# imu_base.net
KiCad netlist of a schematic drawn in EAGLE
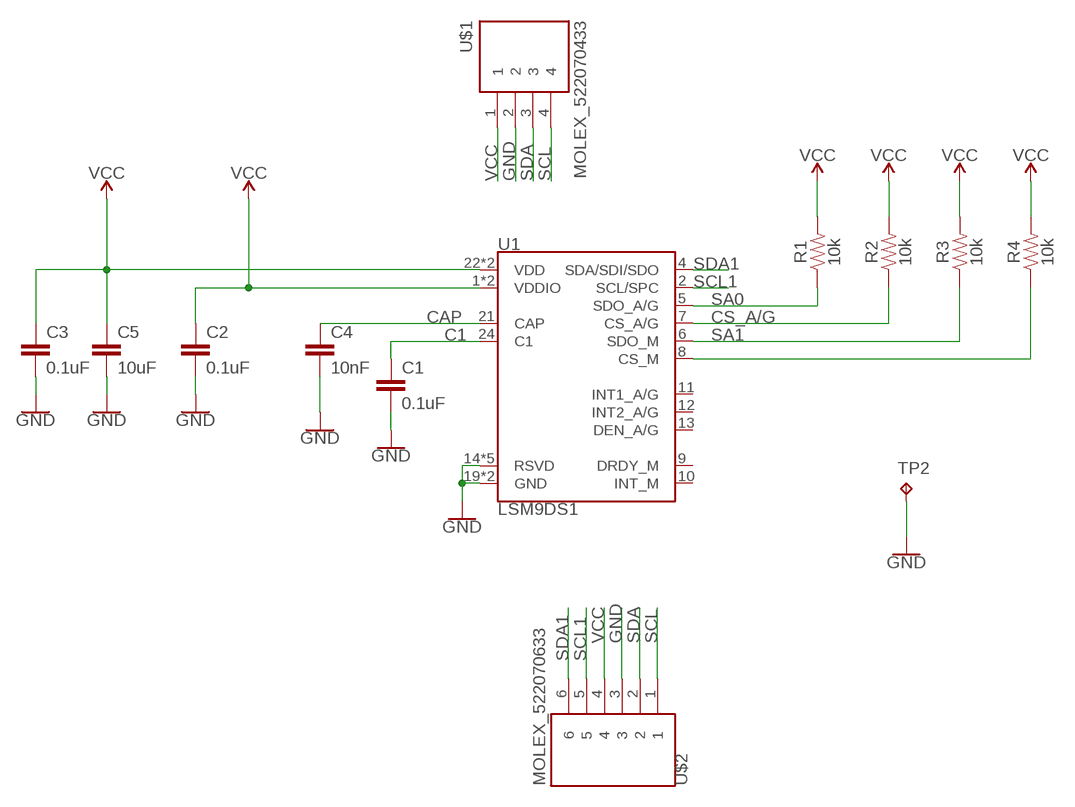
[diagram p0: schematic, sheet 1]

(export (version "E")
  (design (tool "Eeschema 10.0.6"))
  (components
    (comp (ref "C1")
      (value "0.1uF")
      (footprint "eagle-import:0603")
      (libsource (lib "eagle-import") (part "0.1UF-0603-25V-(+80/-20%)"))
    )
    (comp (ref "C2")
      (value "0.1uF")
      (footprint "eagle-import:0603")
      (libsource (lib "eagle-import") (part "0.1UF-0603-25V-(+80/-20%)"))
    )
    (comp (ref "C3")
      (value "0.1uF")
      (footprint "eagle-import:0603")
      (libsource (lib "eagle-import") (part "0.1UF-0603-25V-(+80/-20%)"))
    )
    (comp (ref "C4")
      (value "10nF")
      (footprint "eagle-import:0603")
      (libsource (lib "eagle-import") (part "10NF-0603-50V-10%"))
    )
    (comp (ref "C5")
      (value "10uF")
      (footprint "eagle-import:0603")
      (libsource (lib "eagle-import") (part "10UF-0603-6.3V-20%"))
    )
    (comp (ref "R1")
      (value "10k")
      (footprint "eagle-import:0603")
      (libsource (lib "eagle-import") (part "10KOHM-0603-1/10W-1%"))
    )
    (comp (ref "R2")
      (value "10k")
      (footprint "eagle-import:0603")
      (libsource (lib "eagle-import") (part "10KOHM-0603-1/10W-1%"))
    )
    (comp (ref "R3")
      (value "10k")
      (footprint "eagle-import:0603")
      (libsource (lib "eagle-import") (part "10KOHM-0603-1/10W-1%"))
    )
    (comp (ref "R4")
      (value "10k")
      (footprint "eagle-import:0603")
      (libsource (lib "eagle-import") (part "10KOHM-0603-1/10W-1%"))
    )
    (comp (ref "TP2")
      (value "TPB2,54")
      (footprint "eagle-import:B2,54")
      (libsource (lib "eagle-import") (part "TPB2,54"))
    )
    (comp (ref "U$1")
      (value "MOLEX_522070433")
      (footprint "eagle-import:MOLEX4_1MM")
      (libsource (lib "eagle-import") (part "MOLEX_522070433"))
    )
    (comp (ref "U$2")
      (value "MOLEX_522070633")
      (footprint "eagle-import:MOLEX6_1MM")
      (libsource (lib "eagle-import") (part "MOLEX_522070633"))
    )
    (comp (ref "U1")
      (value "LSM9DS1")
      (footprint "eagle-import:LGA-24-3.5X3")
      (libsource (lib "eagle-import") (part "LSM9DS1"))
    )
  )
  (nets
    (net (code "1") (name "/C1") (class "Default")
      (node (ref "C1") (pin "1") (pinfunction "1_1") (pintype "passive"))
      (node (ref "U1") (pin "24") (pinfunction "C1_24") (pintype "bidirectional"))
    )
    (net (code "2") (name "/CAP") (class "Default")
      (node (ref "C4") (pin "1") (pinfunction "1_1") (pintype "passive"))
      (node (ref "U1") (pin "21") (pinfunction "CAP_21") (pintype "bidirectional"))
    )
    (net (code "3") (name "/CS_A{slash}G") (class "Default")
      (node (ref "R2") (pin "1") (pinfunction "1_1") (pintype "passive"))
      (node (ref "U1") (pin "7") (pinfunction "CS_A/G_7") (pintype "bidirectional"))
    )
    (net (code "4") (name "/SA0") (class "Default")
      (node (ref "R1") (pin "1") (pinfunction "1_1") (pintype "passive"))
      (node (ref "U1") (pin "5") (pinfunction "SDO_A/G_5") (pintype "bidirectional"))
    )
    (net (code "5") (name "/SA1") (class "Default")
      (node (ref "R3") (pin "1") (pinfunction "1_1") (pintype "passive"))
      (node (ref "U1") (pin "6") (pinfunction "SDO_M_6") (pintype "bidirectional"))
    )
    (net (code "6") (name "/SCL") (class "Default")
      (node (ref "U$1") (pin "4") (pinfunction "4_4") (pintype "passive"))
      (node (ref "U$2") (pin "1") (pinfunction "1_1") (pintype "bidirectional"))
    )
    (net (code "7") (name "/SCL1") (class "Default")
      (node (ref "U$2") (pin "5") (pinfunction "5_5") (pintype "bidirectional"))
      (node (ref "U1") (pin "2") (pinfunction "SCL/SPC_2") (pintype "bidirectional"))
    )
    (net (code "8") (name "/SDA") (class "Default")
      (node (ref "U$1") (pin "3") (pinfunction "3_3") (pintype "passive"))
      (node (ref "U$2") (pin "2") (pinfunction "2_2") (pintype "bidirectional"))
    )
    (net (code "9") (name "/SDA1") (class "Default")
      (node (ref "U$2") (pin "6") (pinfunction "6_6") (pintype "bidirectional"))
      (node (ref "U1") (pin "4") (pinfunction "SDA/SDI/SDO_4") (pintype "bidirectional"))
    )
    (net (code "10") (name "GND") (class "Default")
      (node (ref "C1") (pin "2") (pinfunction "2_2") (pintype "passive"))
      (node (ref "C2") (pin "2") (pinfunction "2_2") (pintype "passive"))
      (node (ref "C3") (pin "2") (pinfunction "2_2") (pintype "passive"))
      (node (ref "C4") (pin "2") (pinfunction "2_2") (pintype "passive"))
      (node (ref "C5") (pin "2") (pinfunction "2_2") (pintype "passive"))
      (node (ref "TP2") (pin "TP") (pinfunction "TP_TP") (pintype "input"))
      (node (ref "U$1") (pin "2") (pinfunction "2_2") (pintype "passive"))
      (node (ref "U$2") (pin "3") (pinfunction "3_3") (pintype "bidirectional"))
      (node (ref "U1") (pin "14") (pinfunction "RSVD_14") (pintype "bidirectional"))
      (node (ref "U1") (pin "15") (pinfunction "RSVD_15") (pintype "bidirectional"))
      (node (ref "U1") (pin "16") (pinfunction "RSVD_16") (pintype "bidirectional"))
      (node (ref "U1") (pin "17") (pinfunction "RSVD_17") (pintype "bidirectional"))
      (node (ref "U1") (pin "18") (pinfunction "RSVD_18") (pintype "bidirectional"))
      (node (ref "U1") (pin "19") (pinfunction "GND_19") (pintype "bidirectional"))
      (node (ref "U1") (pin "20") (pinfunction "GND_20") (pintype "bidirectional"))
    )
    (net (code "11") (name "Net-(U1-CS_M)") (class "Default")
      (node (ref "R4") (pin "1") (pinfunction "1_1") (pintype "passive"))
      (node (ref "U1") (pin "8") (pinfunction "CS_M_8") (pintype "bidirectional"))
    )
    (net (code "12") (name "VCC") (class "Default")
      (node (ref "C2") (pin "1") (pinfunction "1_1") (pintype "passive"))
      (node (ref "C3") (pin "1") (pinfunction "1_1") (pintype "passive"))
      (node (ref "C5") (pin "1") (pinfunction "1_1") (pintype "passive"))
      (node (ref "R1") (pin "2") (pinfunction "2_2") (pintype "passive"))
      (node (ref "R2") (pin "2") (pinfunction "2_2") (pintype "passive"))
      (node (ref "R3") (pin "2") (pinfunction "2_2") (pintype "passive"))
      (node (ref "R4") (pin "2") (pinfunction "2_2") (pintype "passive"))
      (node (ref "U$1") (pin "1") (pinfunction "1_1") (pintype "passive"))
      (node (ref "U$2") (pin "4") (pinfunction "4_4") (pintype "bidirectional"))
      (node (ref "U1") (pin "1") (pinfunction "VDDIO_1") (pintype "bidirectional"))
      (node (ref "U1") (pin "22") (pinfunction "VDD_22") (pintype "bidirectional"))
      (node (ref "U1") (pin "23") (pinfunction "VDD_23") (pintype "bidirectional"))
      (node (ref "U1") (pin "3") (pinfunction "VDDIO_3") (pintype "bidirectional"))
    )
    (net (code "13") (name "unconnected-(U1-DEN_A{slash}G-Pad13)") (class "Default")
      (node (ref "U1") (pin "13") (pinfunction "DEN_A/G_13") (pintype "bidirectional"))
    )
    (net (code "14") (name "unconnected-(U1-DRDY_M-Pad9)") (class "Default")
      (node (ref "U1") (pin "9") (pinfunction "DRDY_M_9") (pintype "bidirectional"))
    )
    (net (code "15") (name "unconnected-(U1-INT1_A{slash}G-Pad11)") (class "Default")
      (node (ref "U1") (pin "11") (pinfunction "INT1_A/G_11") (pintype "bidirectional"))
    )
    (net (code "16") (name "unconnected-(U1-INT2_A{slash}G-Pad12)") (class "Default")
      (node (ref "U1") (pin "12") (pinfunction "INT2_A/G_12") (pintype "bidirectional"))
    )
    (net (code "17") (name "unconnected-(U1-INT_M-Pad10)") (class "Default")
      (node (ref "U1") (pin "10") (pinfunction "INT_M_10") (pintype "bidirectional"))
    )
  )
)
